# TE0747.net
KiCad netlist of a schematic drawn in Altium Designer
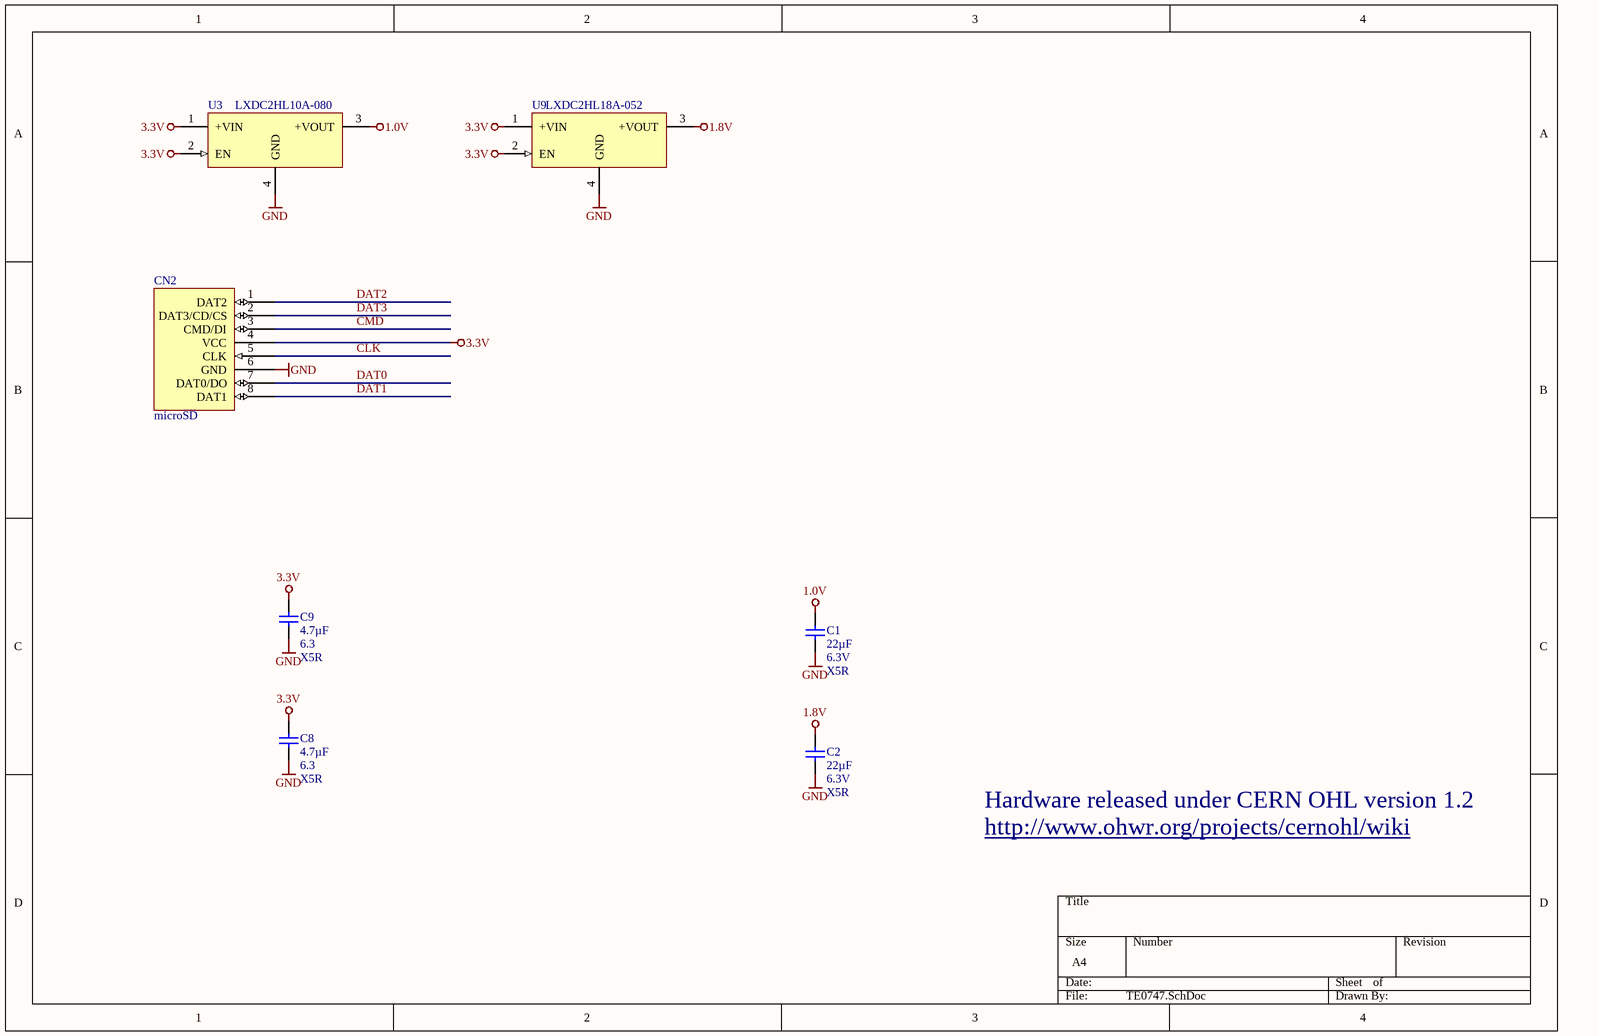
[diagram p0: TE0747.SchDoc]

(export (version "E")
  (design (tool "Eeschema 10.0.6"))
  (components
    (comp (ref "C1")
      (value "22µF")
      (footprint "CAPC1608X90N")
      (description "KON 22µF 6,3V X5R SMD")
      (fields (field (name "VOLTAGE") "6.3V") (field (name "TECHNOLOGY") "X5R"))
      (libsource (lib "TE") (part "CAP-NP"))
    )
    (comp (ref "C2")
      (value "22µF")
      (footprint "CAPC1608X90N")
      (description "KON 22µF 6,3V X5R SMD")
      (fields (field (name "VOLTAGE") "6.3V") (field (name "TECHNOLOGY") "X5R"))
      (libsource (lib "TE") (part "CAP-NP"))
    )
    (comp (ref "C8")
      (value "4.7µF")
      (footprint "CAPC1005X60N")
      (description "KON 4.7µF 6.3V X5R SMD 20%")
      (fields
        (field (name "VOLTAGE") "6.3")
        (field (name "TECHNOLOGY") "X5R")
        (field (name "TOLERANCE") "20%")
      )
      (libsource (lib "TE") (part "CAP-NP"))
    )
    (comp (ref "C9")
      (value "4.7µF")
      (footprint "CAPC1005X60N")
      (description "KON 4.7µF 6.3V X5R SMD 20%")
      (fields
        (field (name "VOLTAGE") "6.3")
        (field (name "TECHNOLOGY") "X5R")
        (field (name "TOLERANCE") "20%")
      )
      (libsource (lib "TE") (part "CAP-NP"))
    )
    (comp (ref "CN2")
      (value "microSD")
      (footprint "uSD_PCB")
      (libsource (lib "uUD-normal_template") (part "microSD_pads"))
    )
    (comp (ref "U3") (value "LXDC2HL10A-080") (footprint "LXDC2HL") (libsource (lib "TE") (part "LXDC2HL")))
    (comp (ref "U9") (value "LXDC2HL18A-052") (footprint "LXDC2HL") (libsource (lib "TE") (part "LXDC2HL")))
  )
  (nets
    (net (code "1") (name "/CLK") (class "Default")
      (node (ref "CN2") (pin "5") (pinfunction "CLK_5") (pintype "input"))
    )
    (net (code "2") (name "/CMD") (class "Default")
      (node (ref "CN2") (pin "3") (pinfunction "CMD/DI_3") (pintype "bidirectional"))
    )
    (net (code "3") (name "/DAT0") (class "Default")
      (node (ref "CN2") (pin "7") (pinfunction "DAT0/DO_7") (pintype "bidirectional"))
    )
    (net (code "4") (name "/DAT1") (class "Default")
      (node (ref "CN2") (pin "8") (pinfunction "DAT1_8") (pintype "bidirectional"))
    )
    (net (code "5") (name "/DAT2") (class "Default")
      (node (ref "CN2") (pin "1") (pinfunction "DAT2_1") (pintype "bidirectional"))
    )
    (net (code "6") (name "/DAT3") (class "Default")
      (node (ref "CN2") (pin "2") (pinfunction "DAT3/CD/CS_2") (pintype "bidirectional"))
    )
    (net (code "7") (name "1.0V") (class "Default")
      (node (ref "C1") (pin "1") (pinfunction "1_1") (pintype "passive"))
      (node (ref "U3") (pin "3") (pinfunction "+VOUT_3") (pintype "power_in"))
    )
    (net (code "8") (name "1.8V") (class "Default")
      (node (ref "C2") (pin "1") (pinfunction "1_1") (pintype "passive"))
      (node (ref "U9") (pin "3") (pinfunction "+VOUT_3") (pintype "power_in"))
    )
    (net (code "9") (name "3.3V") (class "Default")
      (node (ref "C8") (pin "1") (pinfunction "1_1") (pintype "passive"))
      (node (ref "C9") (pin "1") (pinfunction "1_1") (pintype "passive"))
      (node (ref "CN2") (pin "4") (pinfunction "VCC_4") (pintype "power_in"))
      (node (ref "U3") (pin "1") (pinfunction "+VIN_1") (pintype "power_in"))
      (node (ref "U3") (pin "2") (pinfunction "EN_2") (pintype "input"))
      (node (ref "U9") (pin "1") (pinfunction "+VIN_1") (pintype "power_in"))
      (node (ref "U9") (pin "2") (pinfunction "EN_2") (pintype "input"))
    )
    (net (code "10") (name "GND") (class "Default")
      (node (ref "C1") (pin "2") (pinfunction "2_2") (pintype "passive"))
      (node (ref "C2") (pin "2") (pinfunction "2_2") (pintype "passive"))
      (node (ref "C8") (pin "2") (pinfunction "2_2") (pintype "passive"))
      (node (ref "C9") (pin "2") (pinfunction "2_2") (pintype "passive"))
      (node (ref "CN2") (pin "6") (pinfunction "GND_6") (pintype "power_in"))
      (node (ref "U3") (pin "4") (pinfunction "GND_4") (pintype "power_in"))
      (node (ref "U9") (pin "4") (pinfunction "GND_4") (pintype "power_in"))
    )
  )
)
